# Oskar_Kuchejda.net
KiCad netlist of a schematic drawn in EAGLE
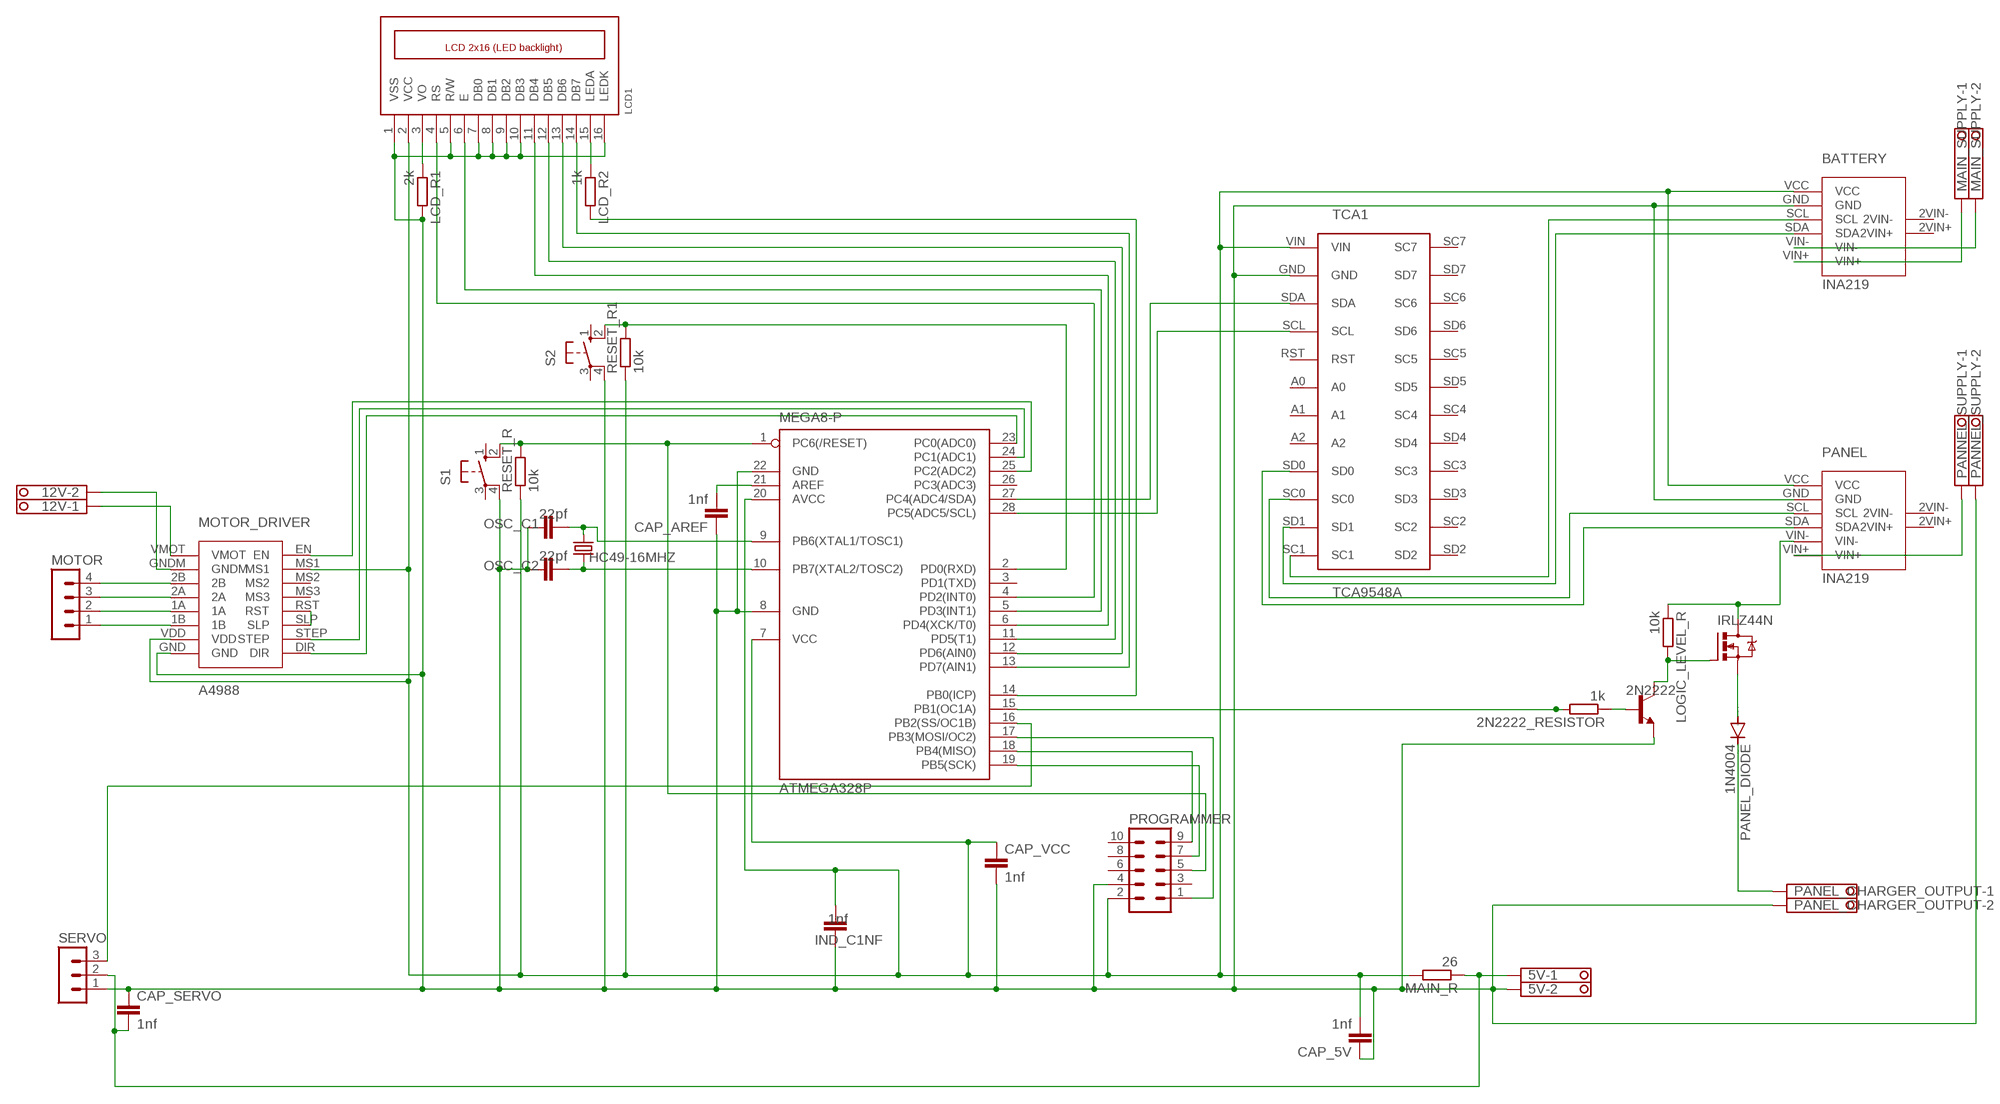
[diagram p0: schematic, sheet 1]

(export (version "E")
  (design (tool "Eeschema 10.0.6"))
  (components
    (comp (ref "2N2222_RESISTOR")
      (value "1k")
      (footprint "eagle-import:0207_2V")
      (libsource (lib "eagle-import") (part "R-EU_0207/2V"))
    )
    (comp (ref "5V")
      (value "TERMINAL-BLOCK-3.5MM-2-PIN-ROUND-PAD")
      (footprint "eagle-import:TERMINAL-BLOCK-2-PIN-3.5MM-ROUND-PAD")
      (libsource (lib "eagle-import") (part "TERMINAL-BLOCK-3.5MM-2-PIN-ROUND-PAD"))
    )
    (comp (ref "12V")
      (value "TERMINAL-BLOCK-3.5MM-2-PIN-ROUND-PAD")
      (footprint "eagle-import:TERMINAL-BLOCK-2-PIN-3.5MM-ROUND-PAD")
      (libsource (lib "eagle-import") (part "TERMINAL-BLOCK-3.5MM-2-PIN-ROUND-PAD"))
    )
    (comp (ref "ATMEGA328P")
      (value "MEGA8-P")
      (footprint "eagle-import:DIL28-3")
      (libsource (lib "eagle-import") (part "MEGA8-P"))
    )
    (comp (ref "BATTERY")
      (value "INA219")
      (footprint "eagle-import:INA219")
      (libsource (lib "eagle-import") (part "INA219"))
    )
    (comp (ref "CAP_5V")
      (value "1nf")
      (footprint "eagle-import:C025-024X044")
      (libsource (lib "eagle-import") (part "C-EU025-024X044"))
    )
    (comp (ref "CAP_AREF")
      (value "1nf")
      (footprint "eagle-import:C025-024X044")
      (libsource (lib "eagle-import") (part "C-EU025-024X044"))
    )
    (comp (ref "CAP_SERVO")
      (value "1nf")
      (footprint "eagle-import:C025-024X044")
      (libsource (lib "eagle-import") (part "C-EU025-024X044"))
    )
    (comp (ref "CAP_VCC")
      (value "1nf")
      (footprint "eagle-import:C025-024X044")
      (libsource (lib "eagle-import") (part "C-EU025-024X044"))
    )
    (comp (ref "HC49-16MHZ")
      (value "CRYTALHC49S")
      (footprint "eagle-import:HC49_S")
      (libsource (lib "eagle-import") (part "CRYTALHC49S"))
    )
    (comp (ref "IND_C1NF")
      (value "1nf")
      (footprint "eagle-import:C025-024X044")
      (libsource (lib "eagle-import") (part "C-EU025-024X044"))
    )
    (comp (ref "IRLZ44N")
      (value "IRF540")
      (footprint "eagle-import:TO220BV")
      (libsource (lib "eagle-import") (part "IRF540"))
    )
    (comp (ref "LCD1")
      (value "LCD_2X16_SIL")
      (footprint "eagle-import:HY-1602F")
      (libsource (lib "eagle-import") (part "LCD_2X16_SIL"))
    )
    (comp (ref "LCD_R1")
      (value "2k")
      (footprint "eagle-import:0207_2V")
      (libsource (lib "eagle-import") (part "R-EU_0207/2V"))
    )
    (comp (ref "LCD_R2")
      (value "1k")
      (footprint "eagle-import:0207_2V")
      (libsource (lib "eagle-import") (part "R-EU_0207/2V"))
    )
    (comp (ref "LOGIC_LEVEL_R")
      (value "10k")
      (footprint "eagle-import:0207_2V")
      (libsource (lib "eagle-import") (part "R-EU_0207/2V"))
    )
    (comp (ref "MAIN_R")
      (value "26")
      (footprint "eagle-import:0207_2V")
      (libsource (lib "eagle-import") (part "R-EU_0207/2V"))
    )
    (comp (ref "MAIN_SUPPLY")
      (value "TERMINAL-BLOCK-3.5MM-2-PIN-ROUND-PAD")
      (footprint "eagle-import:TERMINAL-BLOCK-2-PIN-3.5MM-ROUND-PAD")
      (libsource (lib "eagle-import") (part "TERMINAL-BLOCK-3.5MM-2-PIN-ROUND-PAD"))
    )
    (comp (ref "MOTOR")
      (value "MA04-1")
      (footprint "eagle-import:MA04-1")
      (libsource (lib "eagle-import") (part "MA04-1"))
    )
    (comp (ref "MOTOR_DRIVER")
      (value "A4988")
      (footprint "eagle-import:A4988")
      (libsource (lib "eagle-import") (part "A4988"))
    )
    (comp (ref "OSC_C1")
      (value "22pf")
      (footprint "eagle-import:C025-024X044")
      (libsource (lib "eagle-import") (part "C-EU025-024X044"))
    )
    (comp (ref "OSC_C2")
      (value "22pf")
      (footprint "eagle-import:C025-024X044")
      (libsource (lib "eagle-import") (part "C-EU025-024X044"))
    )
    (comp (ref "PANEL")
      (value "INA219")
      (footprint "eagle-import:INA219")
      (libsource (lib "eagle-import") (part "INA219"))
    )
    (comp (ref "PANEL_CHARGER_OUTPUT")
      (value "TERMINAL-BLOCK-3.5MM-2-PIN-ROUND-PAD")
      (footprint "eagle-import:TERMINAL-BLOCK-2-PIN-3.5MM-ROUND-PAD")
      (libsource (lib "eagle-import") (part "TERMINAL-BLOCK-3.5MM-2-PIN-ROUND-PAD"))
    )
    (comp (ref "PANEL_DIODE")
      (value "1N4004")
      (footprint "eagle-import:DO41-10")
      (libsource (lib "eagle-import") (part "1N4004"))
    )
    (comp (ref "PANNEL_SUPPLY")
      (value "TERMINAL-BLOCK-3.5MM-2-PIN-ROUND-PAD")
      (footprint "eagle-import:TERMINAL-BLOCK-2-PIN-3.5MM-ROUND-PAD")
      (libsource (lib "eagle-import") (part "TERMINAL-BLOCK-3.5MM-2-PIN-ROUND-PAD"))
    )
    (comp (ref "PROGRAMMER")
      (value "MA05-2")
      (footprint "eagle-import:MA05-2")
      (libsource (lib "eagle-import") (part "MA05-2"))
    )
    (comp (ref "RESET_R")
      (value "10k")
      (footprint "eagle-import:0207_2V")
      (libsource (lib "eagle-import") (part "R-EU_0207/2V"))
    )
    (comp (ref "RESET_R1")
      (value "10k")
      (footprint "eagle-import:0207_2V")
      (libsource (lib "eagle-import") (part "R-EU_0207/2V"))
    )
    (comp (ref "S1")
      (value "10-XX")
      (footprint "eagle-import:B3F-10XX")
      (fields (field (name "MPN") "B3F-1000"))
      (libsource (lib "eagle-import") (part "10-XX"))
    )
    (comp (ref "S2")
      (value "10-XX")
      (footprint "eagle-import:B3F-10XX")
      (fields (field (name "MPN") "B3F-1000"))
      (libsource (lib "eagle-import") (part "10-XX"))
    )
    (comp (ref "SERVO")
      (value "MA03-1")
      (footprint "eagle-import:MA03-1")
      (libsource (lib "eagle-import") (part "MA03-1"))
    )
    (comp (ref "T1")
      (value "2N2222")
      (footprint "eagle-import:TO92-EBC-OVAL")
      (libsource (lib "eagle-import") (part "2N2222"))
    )
    (comp (ref "TCA1")
      (value "TCA9548A")
      (footprint "eagle-import:TCA9548A")
      (libsource (lib "eagle-import") (part "TCA9548A"))
    )
  )
  (nets
    (net (code "1") (name "Net-(2N2222_RESISTOR-Pad1)") (class "Default")
      (node (ref "2N2222_RESISTOR") (pin "1") (pinfunction "1_1") (pintype "passive"))
      (node (ref "T1") (pin "B") (pinfunction "B_B") (pintype "passive"))
    )
    (net (code "2") (name "Net-(5VA-K)") (class "Default")
      (node (ref "5V") (pin "1") (pinfunction "K_1") (pintype "passive"))
      (node (ref "CAP_SERVO") (pin "2") (pinfunction "2_2") (pintype "passive"))
      (node (ref "MAIN_R") (pin "1") (pinfunction "1_1") (pintype "passive"))
      (node (ref "SERVO") (pin "2") (pinfunction "2_2") (pintype "passive"))
    )
    (net (code "3") (name "Net-(5VB-K)") (class "Default")
      (node (ref "5V") (pin "2") (pinfunction "K_2") (pintype "passive"))
      (node (ref "ATMEGA328P") (pin "22") (pinfunction "GND_22") (pintype "power_in"))
      (node (ref "ATMEGA328P") (pin "8") (pinfunction "GND_8") (pintype "power_in"))
      (node (ref "BATTERY") (pin "GND") (pinfunction "GND_GND") (pintype "bidirectional"))
      (node (ref "CAP_5V") (pin "1") (pinfunction "1_1") (pintype "passive"))
      (node (ref "CAP_AREF") (pin "1") (pinfunction "1_1") (pintype "passive"))
      (node (ref "CAP_SERVO") (pin "1") (pinfunction "1_1") (pintype "passive"))
      (node (ref "CAP_VCC") (pin "2") (pinfunction "2_2") (pintype "passive"))
      (node (ref "IND_C1NF") (pin "1") (pinfunction "1_1") (pintype "passive"))
      (node (ref "LCD1") (pin "1") (pinfunction "VSS_1") (pintype "power_in"))
      (node (ref "LCD1") (pin "10") (pinfunction "DB3_10") (pintype "bidirectional"))
      (node (ref "LCD1") (pin "16") (pinfunction "LEDK_16") (pintype "passive"))
      (node (ref "LCD1") (pin "5") (pinfunction "R/W_5") (pintype "input"))
      (node (ref "LCD1") (pin "7") (pinfunction "DB0_7") (pintype "bidirectional"))
      (node (ref "LCD1") (pin "8") (pinfunction "DB1_8") (pintype "bidirectional"))
      (node (ref "LCD1") (pin "9") (pinfunction "DB2_9") (pintype "bidirectional"))
      (node (ref "LCD_R1") (pin "2") (pinfunction "2_2") (pintype "passive"))
      (node (ref "MOTOR_DRIVER") (pin "GND") (pinfunction "GND_GND") (pintype "bidirectional"))
      (node (ref "OSC_C1") (pin "1") (pinfunction "1_1") (pintype "passive"))
      (node (ref "OSC_C2") (pin "1") (pinfunction "1_1") (pintype "passive"))
      (node (ref "PANEL") (pin "GND") (pinfunction "GND_GND") (pintype "bidirectional"))
      (node (ref "PANEL_CHARGER_OUTPUT") (pin "2") (pinfunction "K_2") (pintype "passive"))
      (node (ref "PANNEL_SUPPLY") (pin "2") (pinfunction "K_2") (pintype "passive"))
      (node (ref "PROGRAMMER") (pin "4") (pinfunction "4_4") (pintype "passive"))
      (node (ref "S1") (pin "4") (pinfunction "P1_4") (pintype "passive"))
      (node (ref "S2") (pin "4") (pinfunction "P1_4") (pintype "passive"))
      (node (ref "SERVO") (pin "1") (pinfunction "1_1") (pintype "passive"))
      (node (ref "T1") (pin "E") (pinfunction "E_E") (pintype "passive"))
      (node (ref "TCA1") (pin "GND") (pinfunction "GND_GND") (pintype "bidirectional"))
    )
    (net (code "4") (name "Net-(12VA-K)") (class "Default")
      (node (ref "12V") (pin "1") (pinfunction "K_1") (pintype "passive"))
      (node (ref "MOTOR_DRIVER") (pin "VMOT") (pinfunction "VMOT_VMOT") (pintype "bidirectional"))
    )
    (net (code "5") (name "Net-(12VB-K)") (class "Default")
      (node (ref "12V") (pin "2") (pinfunction "K_2") (pintype "passive"))
      (node (ref "MOTOR_DRIVER") (pin "GNDM") (pinfunction "GNDM_GNDM") (pintype "bidirectional"))
    )
    (net (code "6") (name "Net-(ATMEGA328P-AREF)") (class "Default")
      (node (ref "ATMEGA328P") (pin "21") (pinfunction "AREF_21") (pintype "passive"))
      (node (ref "CAP_AREF") (pin "2") (pinfunction "2_2") (pintype "passive"))
    )
    (net (code "7") (name "Net-(ATMEGA328P-AVCC)") (class "Default")
      (node (ref "ATMEGA328P") (pin "20") (pinfunction "AVCC_20") (pintype "power_in"))
      (node (ref "ATMEGA328P") (pin "7") (pinfunction "VCC_7") (pintype "power_in"))
      (node (ref "BATTERY") (pin "VCC") (pinfunction "VCC_VCC") (pintype "bidirectional"))
      (node (ref "CAP_5V") (pin "2") (pinfunction "2_2") (pintype "passive"))
      (node (ref "CAP_VCC") (pin "1") (pinfunction "1_1") (pintype "passive"))
      (node (ref "IND_C1NF") (pin "2") (pinfunction "2_2") (pintype "passive"))
      (node (ref "LCD1") (pin "2") (pinfunction "VCC_2") (pintype "power_in"))
      (node (ref "MAIN_R") (pin "2") (pinfunction "2_2") (pintype "passive"))
      (node (ref "MOTOR_DRIVER") (pin "MS1") (pinfunction "MS1_MS1") (pintype "bidirectional"))
      (node (ref "MOTOR_DRIVER") (pin "VDD") (pinfunction "VDD_VDD") (pintype "bidirectional"))
      (node (ref "PANEL") (pin "VCC") (pinfunction "VCC_VCC") (pintype "bidirectional"))
      (node (ref "PROGRAMMER") (pin "2") (pinfunction "2_2") (pintype "passive"))
      (node (ref "RESET_R") (pin "1") (pinfunction "1_1") (pintype "passive"))
      (node (ref "RESET_R1") (pin "1") (pinfunction "1_1") (pintype "passive"))
      (node (ref "TCA1") (pin "VIN") (pinfunction "VIN_VIN") (pintype "bidirectional"))
    )
    (net (code "8") (name "Net-(ATMEGA328P-PB0(ICP))") (class "Default")
      (node (ref "ATMEGA328P") (pin "14") (pinfunction "PB0(ICP)_14") (pintype "bidirectional"))
      (node (ref "LCD_R2") (pin "2") (pinfunction "2_2") (pintype "passive"))
    )
    (net (code "9") (name "Net-(ATMEGA328P-PB1(OC1A))") (class "Default")
      (node (ref "2N2222_RESISTOR") (pin "2") (pinfunction "2_2") (pintype "passive"))
      (node (ref "ATMEGA328P") (pin "15") (pinfunction "PB1(OC1A)_15") (pintype "bidirectional"))
    )
    (net (code "10") (name "Net-(ATMEGA328P-PB2(SS{slash}OC1B))") (class "Default")
      (node (ref "ATMEGA328P") (pin "16") (pinfunction "PB2(SS/OC1B)_16") (pintype "bidirectional"))
      (node (ref "SERVO") (pin "3") (pinfunction "3_3") (pintype "passive"))
    )
    (net (code "11") (name "Net-(ATMEGA328P-PB3(MOSI{slash}OC2))") (class "Default")
      (node (ref "ATMEGA328P") (pin "17") (pinfunction "PB3(MOSI/OC2)_17") (pintype "bidirectional"))
      (node (ref "PROGRAMMER") (pin "1") (pinfunction "1_1") (pintype "passive"))
    )
    (net (code "12") (name "Net-(ATMEGA328P-PB4(MISO))") (class "Default")
      (node (ref "ATMEGA328P") (pin "18") (pinfunction "PB4(MISO)_18") (pintype "bidirectional"))
      (node (ref "PROGRAMMER") (pin "9") (pinfunction "9_9") (pintype "passive"))
    )
    (net (code "13") (name "Net-(ATMEGA328P-PB5(SCK))") (class "Default")
      (node (ref "ATMEGA328P") (pin "19") (pinfunction "PB5(SCK)_19") (pintype "bidirectional"))
      (node (ref "PROGRAMMER") (pin "7") (pinfunction "7_7") (pintype "passive"))
    )
    (net (code "14") (name "Net-(ATMEGA328P-PB6(XTAL1{slash}TOSC1))") (class "Default")
      (node (ref "ATMEGA328P") (pin "9") (pinfunction "PB6(XTAL1/TOSC1)_9") (pintype "bidirectional"))
      (node (ref "HC49-16MHZ") (pin "1") (pinfunction "1_1") (pintype "passive"))
      (node (ref "OSC_C1") (pin "2") (pinfunction "2_2") (pintype "passive"))
    )
    (net (code "15") (name "Net-(ATMEGA328P-PB7(XTAL2{slash}TOSC2))") (class "Default")
      (node (ref "ATMEGA328P") (pin "10") (pinfunction "PB7(XTAL2/TOSC2)_10") (pintype "bidirectional"))
      (node (ref "HC49-16MHZ") (pin "2") (pinfunction "2_2") (pintype "passive"))
      (node (ref "OSC_C2") (pin "2") (pinfunction "2_2") (pintype "passive"))
    )
    (net (code "16") (name "Net-(ATMEGA328P-PC0(ADC0))") (class "Default")
      (node (ref "ATMEGA328P") (pin "23") (pinfunction "PC0(ADC0)_23") (pintype "bidirectional"))
      (node (ref "MOTOR_DRIVER") (pin "DIR") (pinfunction "DIR_DIR") (pintype "bidirectional"))
    )
    (net (code "17") (name "Net-(ATMEGA328P-PC1(ADC1))") (class "Default")
      (node (ref "ATMEGA328P") (pin "24") (pinfunction "PC1(ADC1)_24") (pintype "bidirectional"))
      (node (ref "MOTOR_DRIVER") (pin "STEP") (pinfunction "STEP_STEP") (pintype "bidirectional"))
    )
    (net (code "18") (name "Net-(ATMEGA328P-PC2(ADC2))") (class "Default")
      (node (ref "ATMEGA328P") (pin "25") (pinfunction "PC2(ADC2)_25") (pintype "bidirectional"))
      (node (ref "MOTOR_DRIVER") (pin "EN") (pinfunction "EN_EN") (pintype "bidirectional"))
    )
    (net (code "19") (name "Net-(ATMEGA328P-PC4(ADC4{slash}SDA))") (class "Default")
      (node (ref "ATMEGA328P") (pin "27") (pinfunction "PC4(ADC4/SDA)_27") (pintype "bidirectional"))
      (node (ref "TCA1") (pin "SDA") (pinfunction "SDA_SDA") (pintype "bidirectional"))
    )
    (net (code "20") (name "Net-(ATMEGA328P-PC5(ADC5{slash}SCL))") (class "Default")
      (node (ref "ATMEGA328P") (pin "28") (pinfunction "PC5(ADC5/SCL)_28") (pintype "bidirectional"))
      (node (ref "TCA1") (pin "SCL") (pinfunction "SCL_SCL") (pintype "bidirectional"))
    )
    (net (code "21") (name "Net-(ATMEGA328P-PC6({slash}RESET))") (class "Default")
      (node (ref "ATMEGA328P") (pin "1") (pinfunction "PC6(/RESET)_1") (pintype "bidirectional"))
      (node (ref "PROGRAMMER") (pin "5") (pinfunction "5_5") (pintype "passive"))
      (node (ref "RESET_R") (pin "2") (pinfunction "2_2") (pintype "passive"))
      (node (ref "S1") (pin "2") (pinfunction "S1_2") (pintype "passive"))
    )
    (net (code "22") (name "Net-(ATMEGA328P-PD0(RXD))") (class "Default")
      (node (ref "ATMEGA328P") (pin "2") (pinfunction "PD0(RXD)_2") (pintype "bidirectional"))
      (node (ref "RESET_R1") (pin "2") (pinfunction "2_2") (pintype "passive"))
      (node (ref "S2") (pin "2") (pinfunction "S1_2") (pintype "passive"))
    )
    (net (code "23") (name "Net-(ATMEGA328P-PD2(INT0))") (class "Default")
      (node (ref "ATMEGA328P") (pin "4") (pinfunction "PD2(INT0)_4") (pintype "bidirectional"))
      (node (ref "LCD1") (pin "4") (pinfunction "RS_4") (pintype "input"))
    )
    (net (code "24") (name "Net-(ATMEGA328P-PD3(INT1))") (class "Default")
      (node (ref "ATMEGA328P") (pin "5") (pinfunction "PD3(INT1)_5") (pintype "bidirectional"))
      (node (ref "LCD1") (pin "6") (pinfunction "E_6") (pintype "input"))
    )
    (net (code "25") (name "Net-(ATMEGA328P-PD4(XCK{slash}T0))") (class "Default")
      (node (ref "ATMEGA328P") (pin "6") (pinfunction "PD4(XCK/T0)_6") (pintype "bidirectional"))
      (node (ref "LCD1") (pin "11") (pinfunction "DB4_11") (pintype "bidirectional"))
    )
    (net (code "26") (name "Net-(ATMEGA328P-PD5(T1))") (class "Default")
      (node (ref "ATMEGA328P") (pin "11") (pinfunction "PD5(T1)_11") (pintype "bidirectional"))
      (node (ref "LCD1") (pin "12") (pinfunction "DB5_12") (pintype "bidirectional"))
    )
    (net (code "27") (name "Net-(ATMEGA328P-PD6(AIN0))") (class "Default")
      (node (ref "ATMEGA328P") (pin "12") (pinfunction "PD6(AIN0)_12") (pintype "bidirectional"))
      (node (ref "LCD1") (pin "13") (pinfunction "DB6_13") (pintype "bidirectional"))
    )
    (net (code "28") (name "Net-(ATMEGA328P-PD7(AIN1))") (class "Default")
      (node (ref "ATMEGA328P") (pin "13") (pinfunction "PD7(AIN1)_13") (pintype "bidirectional"))
      (node (ref "LCD1") (pin "14") (pinfunction "DB7_14") (pintype "bidirectional"))
    )
    (net (code "29") (name "Net-(BATTERY-PadSCL)") (class "Default")
      (node (ref "BATTERY") (pin "SCL") (pinfunction "SCL_SCL") (pintype "bidirectional"))
      (node (ref "TCA1") (pin "SC1") (pinfunction "SC1_SC1") (pintype "bidirectional"))
    )
    (net (code "30") (name "Net-(BATTERY-PadSDA)") (class "Default")
      (node (ref "BATTERY") (pin "SDA") (pinfunction "SDA_SDA") (pintype "bidirectional"))
      (node (ref "TCA1") (pin "SD1") (pinfunction "SD1_SD1") (pintype "bidirectional"))
    )
    (net (code "31") (name "Net-(IRLZ44N-PadD)") (class "Default")
      (node (ref "IRLZ44N") (pin "D") (pinfunction "D_D") (pintype "passive"))
      (node (ref "LOGIC_LEVEL_R") (pin "1") (pinfunction "1_1") (pintype "passive"))
      (node (ref "PANEL") (pin "VIN-") (pinfunction "VIN-_VIN-") (pintype "bidirectional"))
    )
    (net (code "32") (name "Net-(IRLZ44N-PadG)") (class "Default")
      (node (ref "IRLZ44N") (pin "G") (pinfunction "G_G") (pintype "passive"))
      (node (ref "LOGIC_LEVEL_R") (pin "2") (pinfunction "2_2") (pintype "passive"))
      (node (ref "T1") (pin "C") (pinfunction "C_C") (pintype "passive"))
    )
    (net (code "33") (name "Net-(IRLZ44N-PadS)") (class "Default")
      (node (ref "IRLZ44N") (pin "S") (pinfunction "S_S") (pintype "passive"))
      (node (ref "PANEL_DIODE") (pin "A") (pinfunction "A_A") (pintype "passive"))
    )
    (net (code "34") (name "Net-(LCD1-LEDA)") (class "Default")
      (node (ref "LCD1") (pin "15") (pinfunction "LEDA_15") (pintype "passive"))
      (node (ref "LCD_R2") (pin "1") (pinfunction "1_1") (pintype "passive"))
    )
    (net (code "35") (name "Net-(LCD1-VO)") (class "Default")
      (node (ref "LCD1") (pin "3") (pinfunction "VO_3") (pintype "input"))
      (node (ref "LCD_R1") (pin "1") (pinfunction "1_1") (pintype "passive"))
    )
    (net (code "36") (name "Net-(MAIN_SUPPLYA-K)") (class "Default")
      (node (ref "BATTERY") (pin "VIN+") (pinfunction "VIN+_VIN+") (pintype "bidirectional"))
      (node (ref "MAIN_SUPPLY") (pin "1") (pinfunction "K_1") (pintype "passive"))
    )
    (net (code "37") (name "Net-(MAIN_SUPPLYB-K)") (class "Default")
      (node (ref "BATTERY") (pin "VIN-") (pinfunction "VIN-_VIN-") (pintype "bidirectional"))
      (node (ref "MAIN_SUPPLY") (pin "2") (pinfunction "K_2") (pintype "passive"))
    )
    (net (code "38") (name "Net-(MOTOR-Pad1)") (class "Default")
      (node (ref "MOTOR") (pin "1") (pinfunction "1_1") (pintype "passive"))
      (node (ref "MOTOR_DRIVER") (pin "1B") (pinfunction "1B_1B") (pintype "bidirectional"))
    )
    (net (code "39") (name "Net-(MOTOR-Pad2)") (class "Default")
      (node (ref "MOTOR") (pin "2") (pinfunction "2_2") (pintype "passive"))
      (node (ref "MOTOR_DRIVER") (pin "1A") (pinfunction "1A_1A") (pintype "bidirectional"))
    )
    (net (code "40") (name "Net-(MOTOR-Pad3)") (class "Default")
      (node (ref "MOTOR") (pin "3") (pinfunction "3_3") (pintype "passive"))
      (node (ref "MOTOR_DRIVER") (pin "2A") (pinfunction "2A_2A") (pintype "bidirectional"))
    )
    (net (code "41") (name "Net-(MOTOR-Pad4)") (class "Default")
      (node (ref "MOTOR") (pin "4") (pinfunction "4_4") (pintype "passive"))
      (node (ref "MOTOR_DRIVER") (pin "2B") (pinfunction "2B_2B") (pintype "bidirectional"))
    )
    (net (code "42") (name "Net-(MOTOR_DRIVER-PadRST)") (class "Default")
      (node (ref "MOTOR_DRIVER") (pin "RST") (pinfunction "RST_RST") (pintype "bidirectional"))
      (node (ref "MOTOR_DRIVER") (pin "SLP") (pinfunction "SLP_SLP") (pintype "bidirectional"))
    )
    (net (code "43") (name "Net-(PANEL-PadSCL)") (class "Default")
      (node (ref "PANEL") (pin "SCL") (pinfunction "SCL_SCL") (pintype "bidirectional"))
      (node (ref "TCA1") (pin "SC0") (pinfunction "SC0_SC0") (pintype "bidirectional"))
    )
    (net (code "44") (name "Net-(PANEL-PadSDA)") (class "Default")
      (node (ref "PANEL") (pin "SDA") (pinfunction "SDA_SDA") (pintype "bidirectional"))
      (node (ref "TCA1") (pin "SD0") (pinfunction "SD0_SD0") (pintype "bidirectional"))
    )
    (net (code "45") (name "Net-(PANEL_CHARGER_OUTPUTA-K)") (class "Default")
      (node (ref "PANEL_CHARGER_OUTPUT") (pin "1") (pinfunction "K_1") (pintype "passive"))
      (node (ref "PANEL_DIODE") (pin "C") (pinfunction "C_C") (pintype "passive"))
    )
    (net (code "46") (name "Net-(PANNEL_SUPPLYA-K)") (class "Default")
      (node (ref "PANEL") (pin "VIN+") (pinfunction "VIN+_VIN+") (pintype "bidirectional"))
      (node (ref "PANNEL_SUPPLY") (pin "1") (pinfunction "K_1") (pintype "passive"))
    )
    (net (code "47") (name "unconnected-(ATMEGA328P-PC3(ADC3)-Pad26)") (class "Default")
      (node (ref "ATMEGA328P") (pin "26") (pinfunction "PC3(ADC3)_26") (pintype "bidirectional"))
    )
    (net (code "48") (name "unconnected-(ATMEGA328P-PD1(TXD)-Pad3)") (class "Default")
      (node (ref "ATMEGA328P") (pin "3") (pinfunction "PD1(TXD)_3") (pintype "bidirectional"))
    )
    (net (code "49") (name "unconnected-(BATTERY-Pad2VIN+)") (class "Default")
      (node (ref "BATTERY") (pin "2VIN+") (pinfunction "2VIN+_2VIN+") (pintype "bidirectional"))
    )
    (net (code "50") (name "unconnected-(BATTERY-Pad2VIN-)") (class "Default")
      (node (ref "BATTERY") (pin "2VIN-") (pinfunction "2VIN-_2VIN-") (pintype "bidirectional"))
    )
    (net (code "51") (name "unconnected-(MOTOR_DRIVER-PadMS2)") (class "Default")
      (node (ref "MOTOR_DRIVER") (pin "MS2") (pinfunction "MS2_MS2") (pintype "bidirectional"))
    )
    (net (code "52") (name "unconnected-(MOTOR_DRIVER-PadMS3)") (class "Default")
      (node (ref "MOTOR_DRIVER") (pin "MS3") (pinfunction "MS3_MS3") (pintype "bidirectional"))
    )
    (net (code "53") (name "unconnected-(PANEL-Pad2VIN+)") (class "Default")
      (node (ref "PANEL") (pin "2VIN+") (pinfunction "2VIN+_2VIN+") (pintype "bidirectional"))
    )
    (net (code "54") (name "unconnected-(PANEL-Pad2VIN-)") (class "Default")
      (node (ref "PANEL") (pin "2VIN-") (pinfunction "2VIN-_2VIN-") (pintype "bidirectional"))
    )
    (net (code "55") (name "unconnected-(PROGRAMMER-Pad3)") (class "Default")
      (node (ref "PROGRAMMER") (pin "3") (pinfunction "3_3") (pintype "passive"))
    )
    (net (code "56") (name "unconnected-(PROGRAMMER-Pad6)") (class "Default")
      (node (ref "PROGRAMMER") (pin "6") (pinfunction "6_6") (pintype "passive"))
    )
    (net (code "57") (name "unconnected-(PROGRAMMER-Pad8)") (class "Default")
      (node (ref "PROGRAMMER") (pin "8") (pinfunction "8_8") (pintype "passive"))
    )
    (net (code "58") (name "unconnected-(PROGRAMMER-Pad10)") (class "Default")
      (node (ref "PROGRAMMER") (pin "10") (pinfunction "10_10") (pintype "passive"))
    )
    (net (code "59") (name "unconnected-(S1-P-Pad3)") (class "Default")
      (node (ref "S1") (pin "3") (pinfunction "P_3") (pintype "passive"))
    )
    (net (code "60") (name "unconnected-(S1-S-Pad1)") (class "Default")
      (node (ref "S1") (pin "1") (pinfunction "S_1") (pintype "passive"))
    )
    (net (code "61") (name "unconnected-(S2-P-Pad3)") (class "Default")
      (node (ref "S2") (pin "3") (pinfunction "P_3") (pintype "passive"))
    )
    (net (code "62") (name "unconnected-(S2-S-Pad1)") (class "Default")
      (node (ref "S2") (pin "1") (pinfunction "S_1") (pintype "passive"))
    )
    (net (code "63") (name "unconnected-(TCA1-PadA0)") (class "Default")
      (node (ref "TCA1") (pin "A0") (pinfunction "A0_A0") (pintype "bidirectional"))
    )
    (net (code "64") (name "unconnected-(TCA1-PadA1)") (class "Default")
      (node (ref "TCA1") (pin "A1") (pinfunction "A1_A1") (pintype "bidirectional"))
    )
    (net (code "65") (name "unconnected-(TCA1-PadA2)") (class "Default")
      (node (ref "TCA1") (pin "A2") (pinfunction "A2_A2") (pintype "bidirectional"))
    )
    (net (code "66") (name "unconnected-(TCA1-PadRST)") (class "Default")
      (node (ref "TCA1") (pin "RST") (pinfunction "RST_RST") (pintype "bidirectional"))
    )
    (net (code "67") (name "unconnected-(TCA1-PadSC2)") (class "Default")
      (node (ref "TCA1") (pin "SC2") (pinfunction "SC2_SC2") (pintype "bidirectional"))
    )
    (net (code "68") (name "unconnected-(TCA1-PadSC3)") (class "Default")
      (node (ref "TCA1") (pin "SC3") (pinfunction "SC3_SC3") (pintype "bidirectional"))
    )
    (net (code "69") (name "unconnected-(TCA1-PadSC4)") (class "Default")
      (node (ref "TCA1") (pin "SC4") (pinfunction "SC4_SC4") (pintype "bidirectional"))
    )
    (net (code "70") (name "unconnected-(TCA1-PadSC5)") (class "Default")
      (node (ref "TCA1") (pin "SC5") (pinfunction "SC5_SC5") (pintype "bidirectional"))
    )
    (net (code "71") (name "unconnected-(TCA1-PadSC6)") (class "Default")
      (node (ref "TCA1") (pin "SC6") (pinfunction "SC6_SC6") (pintype "bidirectional"))
    )
    (net (code "72") (name "unconnected-(TCA1-PadSC7)") (class "Default")
      (node (ref "TCA1") (pin "SC7") (pinfunction "SC7_SC7") (pintype "bidirectional"))
    )
    (net (code "73") (name "unconnected-(TCA1-PadSD2)") (class "Default")
      (node (ref "TCA1") (pin "SD2") (pinfunction "SD2_SD2") (pintype "bidirectional"))
    )
    (net (code "74") (name "unconnected-(TCA1-PadSD3)") (class "Default")
      (node (ref "TCA1") (pin "SD3") (pinfunction "SD3_SD3") (pintype "bidirectional"))
    )
    (net (code "75") (name "unconnected-(TCA1-PadSD4)") (class "Default")
      (node (ref "TCA1") (pin "SD4") (pinfunction "SD4_SD4") (pintype "bidirectional"))
    )
    (net (code "76") (name "unconnected-(TCA1-PadSD5)") (class "Default")
      (node (ref "TCA1") (pin "SD5") (pinfunction "SD5_SD5") (pintype "bidirectional"))
    )
    (net (code "77") (name "unconnected-(TCA1-PadSD6)") (class "Default")
      (node (ref "TCA1") (pin "SD6") (pinfunction "SD6_SD6") (pintype "bidirectional"))
    )
    (net (code "78") (name "unconnected-(TCA1-PadSD7)") (class "Default")
      (node (ref "TCA1") (pin "SD7") (pinfunction "SD7_SD7") (pintype "bidirectional"))
    )
  )
)
